# YSOLAR_PANEL.net
KiCad netlist of a schematic drawn in EAGLE
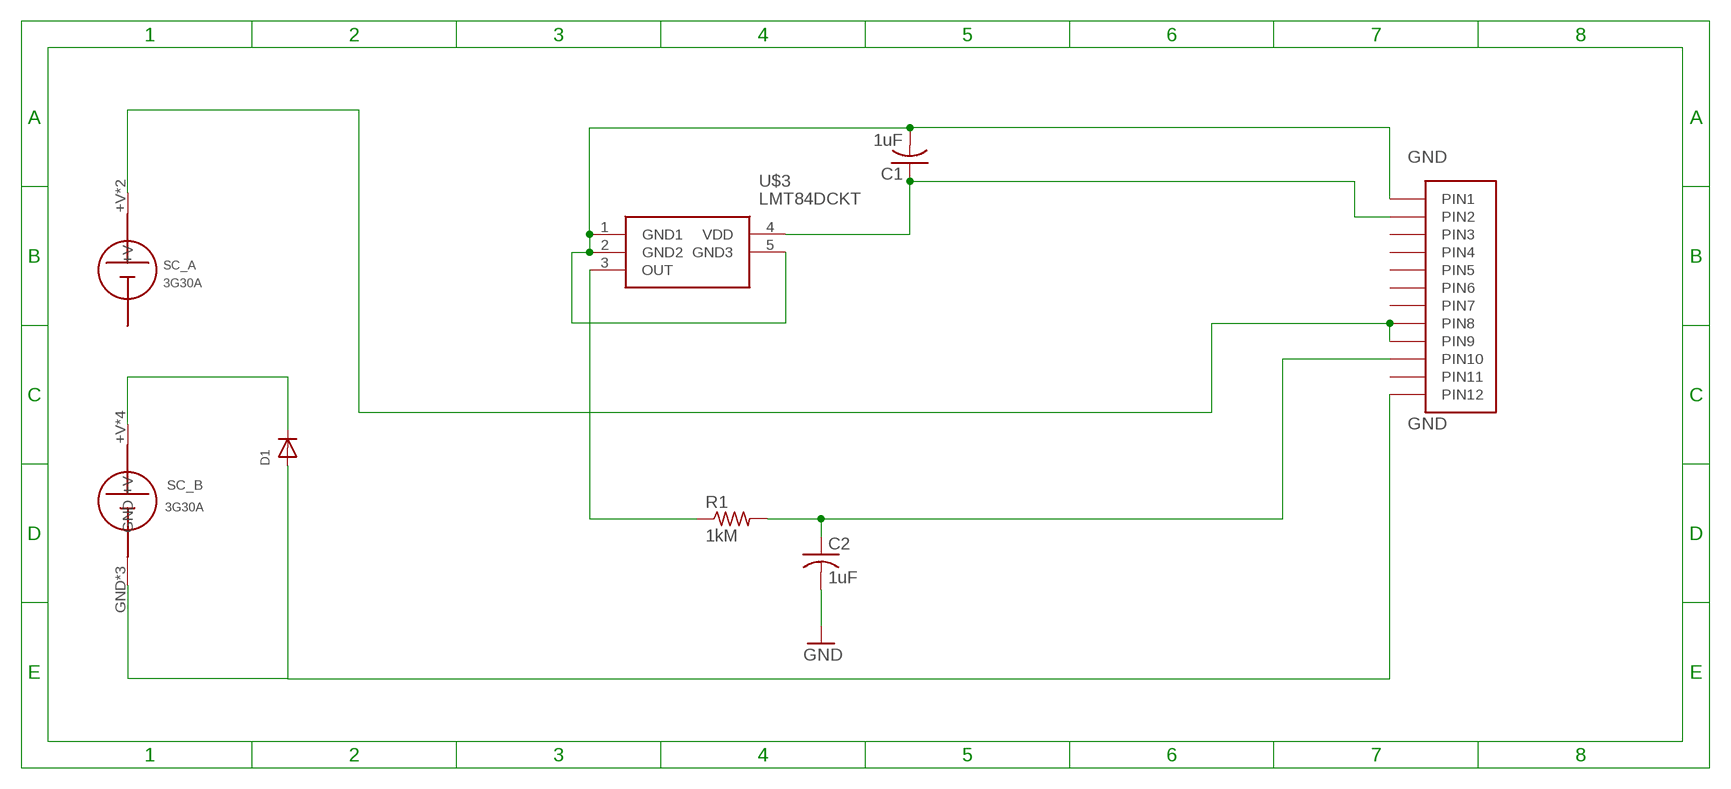
[diagram p0: schematic, sheet 1]

(export (version "E")
  (design (tool "Eeschema 10.0.6"))
  (components
    (comp (ref "C1")
      (value "1uF")
      (footprint "eagle-import:C0805")
      (libsource (lib "eagle-import") (part "C-USC0805"))
    )
    (comp (ref "C2")
      (value "1uF")
      (footprint "eagle-import:C0805")
      (libsource (lib "eagle-import") (part "C-USC0805"))
    )
    (comp (ref "D1")
      (value "DIODE_SOD-123FL")
      (footprint "eagle-import:SOD-123FL")
      (libsource (lib "eagle-import") (part "DIODE_SOD-123FL"))
    )
    (comp (ref "R1")
      (value "1kM")
      (footprint "eagle-import:R0402")
      (libsource (lib "eagle-import") (part "R-US_R0402"))
    )
    (comp (ref "SOLARCELL_A")
      (value "SC_A")
      (footprint "eagle-import:SC_A")
      (libsource (lib "eagle-import") (part "SC_A"))
    )
    (comp (ref "SOLARCELL_B")
      (value "SC_B")
      (footprint "eagle-import:SC_B")
      (libsource (lib "eagle-import") (part "SC_B"))
    )
    (comp (ref "U$1")
      (value "HEADER12PIN")
      (footprint "eagle-import:HEADER12PIN")
      (libsource (lib "eagle-import") (part "HEADER12PIN"))
    )
    (comp (ref "U$3")
      (value "LMT84DCKT")
      (footprint "eagle-import:SOT65P210X110-5N")
      (fields (field (name "RS_PART_NUMBER") "8115860"))
      (libsource (lib "eagle-import") (part "LMT84DCKT"))
    )
  )
  (nets
    (net (code "1") (name "GND") (class "Default")
      (node (ref "C1") (pin "2") (pinfunction "2_2") (pintype "passive"))
      (node (ref "C2") (pin "2") (pinfunction "2_2") (pintype "passive"))
      (node (ref "D1") (pin "A") (pinfunction "A_A") (pintype "passive"))
      (node (ref "SOLARCELL_B") (pin "GND") (pinfunction "GND_GND") (pintype "bidirectional"))
      (node (ref "SOLARCELL_B") (pin "GND1") (pinfunction "GND_GND1") (pintype "bidirectional"))
      (node (ref "SOLARCELL_B") (pin "GND2") (pinfunction "GND_GND2") (pintype "bidirectional"))
      (node (ref "U$1") (pin "P1") (pinfunction "PIN1_P1") (pintype "bidirectional"))
      (node (ref "U$1") (pin "P12") (pinfunction "PIN12_P12") (pintype "bidirectional"))
      (node (ref "U$3") (pin "1") (pinfunction "GND1_1") (pintype "power_in"))
      (node (ref "U$3") (pin "2") (pinfunction "GND2_2") (pintype "power_in"))
      (node (ref "U$3") (pin "5") (pinfunction "GND3_5") (pintype "power_in"))
    )
    (net (code "2") (name "Net-(D1-PadC)") (class "Default")
      (node (ref "D1") (pin "C") (pinfunction "C_C") (pintype "passive"))
      (node (ref "SOLARCELL_B") (pin "+V") (pinfunction "+V_+V") (pintype "bidirectional"))
      (node (ref "SOLARCELL_B") (pin "+V2") (pinfunction "+V_+V2") (pintype "bidirectional"))
      (node (ref "SOLARCELL_B") (pin "+V3") (pinfunction "+V_+V3") (pintype "bidirectional"))
      (node (ref "SOLARCELL_B") (pin "+V4") (pinfunction "+V_+V4") (pintype "bidirectional"))
    )
    (net (code "3") (name "Net-(U$1-PIN2)") (class "Default")
      (node (ref "C1") (pin "1") (pinfunction "1_1") (pintype "passive"))
      (node (ref "U$1") (pin "P2") (pinfunction "PIN2_P2") (pintype "bidirectional"))
      (node (ref "U$3") (pin "4") (pinfunction "VDD_4") (pintype "power_in"))
    )
    (net (code "4") (name "Net-(U$1-PIN8)") (class "Default")
      (node (ref "SOLARCELL_A") (pin "+V") (pinfunction "+V_+V") (pintype "bidirectional"))
      (node (ref "SOLARCELL_A") (pin "+V1") (pinfunction "+V_+V1") (pintype "bidirectional"))
      (node (ref "U$1") (pin "P8") (pinfunction "PIN8_P8") (pintype "bidirectional"))
      (node (ref "U$1") (pin "P9") (pinfunction "PIN9_P9") (pintype "bidirectional"))
    )
    (net (code "5") (name "Net-(U$1-PIN10)") (class "Default")
      (node (ref "C2") (pin "1") (pinfunction "1_1") (pintype "passive"))
      (node (ref "R1") (pin "2") (pinfunction "2_2") (pintype "passive"))
      (node (ref "U$1") (pin "P10") (pinfunction "PIN10_P10") (pintype "bidirectional"))
    )
    (net (code "6") (name "Net-(U$3-OUT)") (class "Default")
      (node (ref "R1") (pin "1") (pinfunction "1_1") (pintype "passive"))
      (node (ref "U$3") (pin "3") (pinfunction "OUT_3") (pintype "output"))
    )
    (net (code "7") (name "unconnected-(U$1-PIN3-PadP3)") (class "Default")
      (node (ref "U$1") (pin "P3") (pinfunction "PIN3_P3") (pintype "bidirectional"))
    )
    (net (code "8") (name "unconnected-(U$1-PIN4-PadP4)") (class "Default")
      (node (ref "U$1") (pin "P4") (pinfunction "PIN4_P4") (pintype "bidirectional"))
    )
    (net (code "9") (name "unconnected-(U$1-PIN5-PadP5)") (class "Default")
      (node (ref "U$1") (pin "P5") (pinfunction "PIN5_P5") (pintype "bidirectional"))
    )
    (net (code "10") (name "unconnected-(U$1-PIN6-PadP6)") (class "Default")
      (node (ref "U$1") (pin "P6") (pinfunction "PIN6_P6") (pintype "bidirectional"))
    )
    (net (code "11") (name "unconnected-(U$1-PIN7-PadP7)") (class "Default")
      (node (ref "U$1") (pin "P7") (pinfunction "PIN7_P7") (pintype "bidirectional"))
    )
    (net (code "12") (name "unconnected-(U$1-PIN11-PadP11)") (class "Default")
      (node (ref "U$1") (pin "P11") (pinfunction "PIN11_P11") (pintype "bidirectional"))
    )
  )
)
